# untitled.net
KiCad netlist of a schematic drawn in EAGLE
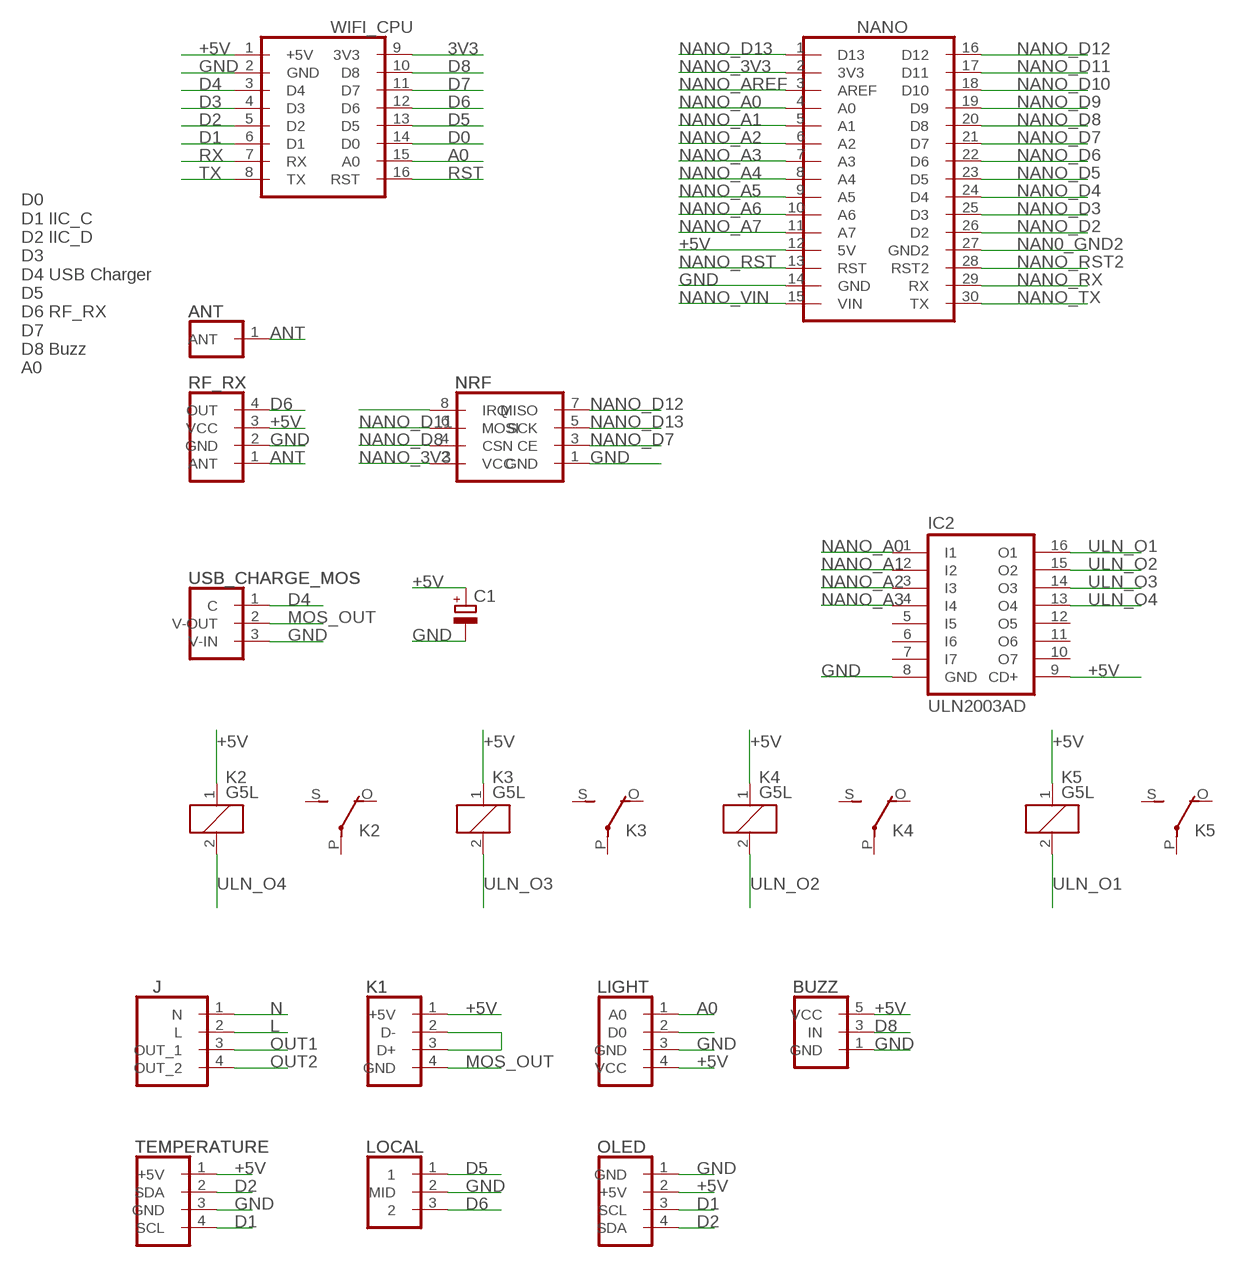
[diagram p0: schematic, sheet 1]

(export (version "E")
  (design (tool "Eeschema 10.0.6"))
  (components
    (comp (ref "ANT")
      (value "ANT_315")
      (footprint "eagle-import:ANT_315")
      (libsource (lib "eagle-import") (part "ANT_315"))
    )
    (comp (ref "BUZZ")
      (value "BUZZ_MODULE")
      (footprint "eagle-import:BUZZ_MODULE")
      (libsource (lib "eagle-import") (part "BUZZ_MODULE"))
    )
    (comp (ref "C1")
      (value "CPOL-EUE5-5")
      (footprint "eagle-import:E5-5")
      (libsource (lib "eagle-import") (part "CPOL-EUE5-5"))
    )
    (comp (ref "IC2")
      (value "ULN2003AD")
      (footprint "eagle-import:SO16")
      (libsource (lib "eagle-import") (part "ULN2003AD"))
    )
    (comp (ref "J")
      (value "OUT_HEAD_4_AC_2CH")
      (footprint "eagle-import:OUT_HEAD_4_AC_2CH")
      (libsource (lib "eagle-import") (part "OUT_HEAD_4_AC_2CH"))
    )
    (comp (ref "K1")
      (value "USB_OUTUSB_V")
      (footprint "eagle-import:USB_V_OUT")
      (libsource (lib "eagle-import") (part "USB_OUTUSB_V"))
    )
    (comp (ref "K2")
      (value "G5L")
      (footprint "eagle-import:G5LE")
      (libsource (lib "eagle-import") (part "G5L"))
    )
    (comp (ref "K3")
      (value "G5L")
      (footprint "eagle-import:G5LE")
      (libsource (lib "eagle-import") (part "G5L"))
    )
    (comp (ref "K4")
      (value "G5L")
      (footprint "eagle-import:G5LE")
      (libsource (lib "eagle-import") (part "G5L"))
    )
    (comp (ref "K5")
      (value "G5L")
      (footprint "eagle-import:G5LE")
      (libsource (lib "eagle-import") (part "G5L"))
    )
    (comp (ref "LIGHT")
      (value "LIGHT_DEC")
      (footprint "eagle-import:LIGHT_DEC")
      (libsource (lib "eagle-import") (part "LIGHT_DEC"))
    )
    (comp (ref "LOCAL")
      (value "SELECT_3")
      (footprint "eagle-import:SELECT_3")
      (libsource (lib "eagle-import") (part "SELECT_3"))
    )
    (comp (ref "NANO")
      (value "ARDUINO_NANO")
      (footprint "eagle-import:ARDUINO_NANO")
      (libsource (lib "eagle-import") (part "ARDUINO_NANO"))
    )
    (comp (ref "NRF")
      (value "NRF24L01_MODULE")
      (footprint "eagle-import:NRF24L01")
      (libsource (lib "eagle-import") (part "NRF24L01_MODULE"))
    )
    (comp (ref "OLED")
      (value "IIC_OLED")
      (footprint "eagle-import:IIC_OLED")
      (libsource (lib "eagle-import") (part "IIC_OLED"))
    )
    (comp (ref "RF_RX")
      (value "315MHZ_RX_SMT")
      (footprint "eagle-import:315MHZ_RX_SMT")
      (libsource (lib "eagle-import") (part "315MHZ_RX_SMT"))
    )
    (comp (ref "TEMPERATURE")
      (value "IIC_TEMPERATURE")
      (footprint "eagle-import:IIC_TEMPERATURE")
      (libsource (lib "eagle-import") (part "IIC_TEMPERATURE"))
    )
    (comp (ref "USB_CHARGE_MOS")
      (value "MOS_IRF520")
      (footprint "eagle-import:MOS_IRF520")
      (libsource (lib "eagle-import") (part "MOS_IRF520"))
    )
    (comp (ref "WIFI_CPU")
      (value "ESP8266_MINI")
      (footprint "eagle-import:ESP8266_MINI")
      (libsource (lib "eagle-import") (part "ESP8266_MINI"))
    )
  )
  (nets
    (net (code "1") (name "/+5V") (class "Default")
      (node (ref "BUZZ") (pin "5") (pinfunction "VCC_5") (pintype "bidirectional"))
      (node (ref "C1") (pin "+") (pinfunction "+_+") (pintype "passive"))
      (node (ref "IC2") (pin "9") (pinfunction "CD+_9") (pintype "passive"))
      (node (ref "K1") (pin "1") (pinfunction "+5V_1") (pintype "bidirectional"))
      (node (ref "K2") (pin "1") (pinfunction "1_1") (pintype "passive"))
      (node (ref "K3") (pin "1") (pinfunction "1_1") (pintype "passive"))
      (node (ref "K4") (pin "1") (pinfunction "1_1") (pintype "passive"))
      (node (ref "K5") (pin "1") (pinfunction "1_1") (pintype "passive"))
      (node (ref "LIGHT") (pin "4") (pinfunction "VCC_4") (pintype "bidirectional"))
      (node (ref "NANO") (pin "12") (pinfunction "5V_12") (pintype "bidirectional"))
      (node (ref "OLED") (pin "2") (pinfunction "+5V_2") (pintype "bidirectional"))
      (node (ref "RF_RX") (pin "3") (pinfunction "VCC_3") (pintype "bidirectional"))
      (node (ref "TEMPERATURE") (pin "1") (pinfunction "+5V_1") (pintype "bidirectional"))
      (node (ref "WIFI_CPU") (pin "1") (pinfunction "+5V_1") (pintype "bidirectional"))
    )
    (net (code "2") (name "/3V3") (class "Default")
      (node (ref "WIFI_CPU") (pin "9") (pinfunction "3V3_9") (pintype "bidirectional"))
    )
    (net (code "3") (name "/A0") (class "Default")
      (node (ref "LIGHT") (pin "1") (pinfunction "A0_1") (pintype "bidirectional"))
      (node (ref "WIFI_CPU") (pin "15") (pinfunction "A0_15") (pintype "bidirectional"))
    )
    (net (code "4") (name "/ANT") (class "Default")
      (node (ref "ANT") (pin "1") (pinfunction "ANT_1") (pintype "bidirectional"))
      (node (ref "RF_RX") (pin "1") (pinfunction "ANT_1") (pintype "bidirectional"))
    )
    (net (code "5") (name "/D0") (class "Default")
      (node (ref "WIFI_CPU") (pin "14") (pinfunction "D0_14") (pintype "bidirectional"))
    )
    (net (code "6") (name "/D1") (class "Default")
      (node (ref "OLED") (pin "3") (pinfunction "SCL_3") (pintype "bidirectional"))
      (node (ref "TEMPERATURE") (pin "4") (pinfunction "SCL_4") (pintype "bidirectional"))
      (node (ref "WIFI_CPU") (pin "6") (pinfunction "D1_6") (pintype "bidirectional"))
    )
    (net (code "7") (name "/D2") (class "Default")
      (node (ref "OLED") (pin "4") (pinfunction "SDA_4") (pintype "bidirectional"))
      (node (ref "TEMPERATURE") (pin "2") (pinfunction "SDA_2") (pintype "bidirectional"))
      (node (ref "WIFI_CPU") (pin "5") (pinfunction "D2_5") (pintype "bidirectional"))
    )
    (net (code "8") (name "/D3") (class "Default")
      (node (ref "WIFI_CPU") (pin "4") (pinfunction "D3_4") (pintype "bidirectional"))
    )
    (net (code "9") (name "/D4") (class "Default")
      (node (ref "USB_CHARGE_MOS") (pin "1") (pinfunction "C_1") (pintype "bidirectional"))
      (node (ref "WIFI_CPU") (pin "3") (pinfunction "D4_3") (pintype "bidirectional"))
    )
    (net (code "10") (name "/D5") (class "Default")
      (node (ref "LOCAL") (pin "1") (pinfunction "1_1") (pintype "bidirectional"))
      (node (ref "WIFI_CPU") (pin "13") (pinfunction "D5_13") (pintype "bidirectional"))
    )
    (net (code "11") (name "/D6") (class "Default")
      (node (ref "LOCAL") (pin "3") (pinfunction "2_3") (pintype "bidirectional"))
      (node (ref "RF_RX") (pin "4") (pinfunction "OUT_4") (pintype "bidirectional"))
      (node (ref "WIFI_CPU") (pin "12") (pinfunction "D6_12") (pintype "bidirectional"))
    )
    (net (code "12") (name "/D7") (class "Default")
      (node (ref "WIFI_CPU") (pin "11") (pinfunction "D7_11") (pintype "bidirectional"))
    )
    (net (code "13") (name "/D8") (class "Default")
      (node (ref "BUZZ") (pin "3") (pinfunction "IN_3") (pintype "bidirectional"))
      (node (ref "WIFI_CPU") (pin "10") (pinfunction "D8_10") (pintype "bidirectional"))
    )
    (net (code "14") (name "/GND") (class "Default")
      (node (ref "BUZZ") (pin "1") (pinfunction "GND_1") (pintype "bidirectional"))
      (node (ref "C1") (pin "-") (pinfunction "-_-") (pintype "passive"))
      (node (ref "IC2") (pin "8") (pinfunction "GND_8") (pintype "power_in"))
      (node (ref "LIGHT") (pin "3") (pinfunction "GND_3") (pintype "bidirectional"))
      (node (ref "LOCAL") (pin "2") (pinfunction "MID_2") (pintype "bidirectional"))
      (node (ref "NANO") (pin "14") (pinfunction "GND_14") (pintype "bidirectional"))
      (node (ref "NRF") (pin "1") (pinfunction "GND_1") (pintype "bidirectional"))
      (node (ref "OLED") (pin "1") (pinfunction "GND_1") (pintype "bidirectional"))
      (node (ref "RF_RX") (pin "2") (pinfunction "GND_2") (pintype "bidirectional"))
      (node (ref "TEMPERATURE") (pin "3") (pinfunction "GND_3") (pintype "bidirectional"))
      (node (ref "USB_CHARGE_MOS") (pin "3") (pinfunction "V-IN_3") (pintype "bidirectional"))
      (node (ref "WIFI_CPU") (pin "2") (pinfunction "GND_2") (pintype "bidirectional"))
    )
    (net (code "15") (name "/L") (class "Default")
      (node (ref "J") (pin "2") (pinfunction "L_2") (pintype "bidirectional"))
    )
    (net (code "16") (name "/MOS_OUT") (class "Default")
      (node (ref "K1") (pin "4") (pinfunction "GND_4") (pintype "bidirectional"))
      (node (ref "USB_CHARGE_MOS") (pin "2") (pinfunction "V-OUT_2") (pintype "bidirectional"))
    )
    (net (code "17") (name "/N") (class "Default")
      (node (ref "J") (pin "1") (pinfunction "N_1") (pintype "bidirectional"))
    )
    (net (code "18") (name "/NAN0_GND2") (class "Default")
      (node (ref "NANO") (pin "27") (pinfunction "GND2_27") (pintype "bidirectional"))
    )
    (net (code "19") (name "/NANO_3V3") (class "Default")
      (node (ref "NANO") (pin "2") (pinfunction "3V3_2") (pintype "bidirectional"))
      (node (ref "NRF") (pin "2") (pinfunction "VCC_2") (pintype "bidirectional"))
    )
    (net (code "20") (name "/NANO_A0") (class "Default")
      (node (ref "IC2") (pin "1") (pinfunction "I1_1") (pintype "input"))
      (node (ref "NANO") (pin "4") (pinfunction "A0_4") (pintype "bidirectional"))
    )
    (net (code "21") (name "/NANO_A1") (class "Default")
      (node (ref "IC2") (pin "2") (pinfunction "I2_2") (pintype "input"))
      (node (ref "NANO") (pin "5") (pinfunction "A1_5") (pintype "bidirectional"))
    )
    (net (code "22") (name "/NANO_A2") (class "Default")
      (node (ref "IC2") (pin "3") (pinfunction "I3_3") (pintype "input"))
      (node (ref "NANO") (pin "6") (pinfunction "A2_6") (pintype "bidirectional"))
    )
    (net (code "23") (name "/NANO_A3") (class "Default")
      (node (ref "IC2") (pin "4") (pinfunction "I4_4") (pintype "input"))
      (node (ref "NANO") (pin "7") (pinfunction "A3_7") (pintype "bidirectional"))
    )
    (net (code "24") (name "/NANO_A4") (class "Default")
      (node (ref "NANO") (pin "8") (pinfunction "A4_8") (pintype "bidirectional"))
    )
    (net (code "25") (name "/NANO_A5") (class "Default")
      (node (ref "NANO") (pin "9") (pinfunction "A5_9") (pintype "bidirectional"))
    )
    (net (code "26") (name "/NANO_A6") (class "Default")
      (node (ref "NANO") (pin "10") (pinfunction "A6_10") (pintype "bidirectional"))
    )
    (net (code "27") (name "/NANO_A7") (class "Default")
      (node (ref "NANO") (pin "11") (pinfunction "A7_11") (pintype "bidirectional"))
    )
    (net (code "28") (name "/NANO_AREF") (class "Default")
      (node (ref "NANO") (pin "3") (pinfunction "AREF_3") (pintype "bidirectional"))
    )
    (net (code "29") (name "/NANO_D2") (class "Default")
      (node (ref "NANO") (pin "26") (pinfunction "D2_26") (pintype "bidirectional"))
    )
    (net (code "30") (name "/NANO_D3") (class "Default")
      (node (ref "NANO") (pin "25") (pinfunction "D3_25") (pintype "bidirectional"))
    )
    (net (code "31") (name "/NANO_D4") (class "Default")
      (node (ref "NANO") (pin "24") (pinfunction "D4_24") (pintype "bidirectional"))
    )
    (net (code "32") (name "/NANO_D5") (class "Default")
      (node (ref "NANO") (pin "23") (pinfunction "D5_23") (pintype "bidirectional"))
    )
    (net (code "33") (name "/NANO_D6") (class "Default")
      (node (ref "NANO") (pin "22") (pinfunction "D6_22") (pintype "bidirectional"))
    )
    (net (code "34") (name "/NANO_D7") (class "Default")
      (node (ref "NANO") (pin "21") (pinfunction "D7_21") (pintype "bidirectional"))
      (node (ref "NRF") (pin "3") (pinfunction "CE_3") (pintype "bidirectional"))
    )
    (net (code "35") (name "/NANO_D8") (class "Default")
      (node (ref "NANO") (pin "20") (pinfunction "D8_20") (pintype "bidirectional"))
      (node (ref "NRF") (pin "4") (pinfunction "CSN_4") (pintype "bidirectional"))
    )
    (net (code "36") (name "/NANO_D9") (class "Default")
      (node (ref "NANO") (pin "19") (pinfunction "D9_19") (pintype "bidirectional"))
    )
    (net (code "37") (name "/NANO_D10") (class "Default")
      (node (ref "NANO") (pin "18") (pinfunction "D10_18") (pintype "bidirectional"))
    )
    (net (code "38") (name "/NANO_D11") (class "Default")
      (node (ref "NANO") (pin "17") (pinfunction "D11_17") (pintype "bidirectional"))
      (node (ref "NRF") (pin "6") (pinfunction "MOSI_6") (pintype "bidirectional"))
    )
    (net (code "39") (name "/NANO_D12") (class "Default")
      (node (ref "NANO") (pin "16") (pinfunction "D12_16") (pintype "bidirectional"))
      (node (ref "NRF") (pin "7") (pinfunction "MISO_7") (pintype "bidirectional"))
    )
    (net (code "40") (name "/NANO_D13") (class "Default")
      (node (ref "NANO") (pin "1") (pinfunction "D13_1") (pintype "bidirectional"))
      (node (ref "NRF") (pin "5") (pinfunction "SCK_5") (pintype "bidirectional"))
    )
    (net (code "41") (name "/NANO_RST") (class "Default")
      (node (ref "NANO") (pin "13") (pinfunction "RST_13") (pintype "bidirectional"))
    )
    (net (code "42") (name "/NANO_RST2") (class "Default")
      (node (ref "NANO") (pin "28") (pinfunction "RST2_28") (pintype "bidirectional"))
    )
    (net (code "43") (name "/NANO_RX") (class "Default")
      (node (ref "NANO") (pin "29") (pinfunction "RX_29") (pintype "bidirectional"))
    )
    (net (code "44") (name "/NANO_TX") (class "Default")
      (node (ref "NANO") (pin "30") (pinfunction "TX_30") (pintype "bidirectional"))
    )
    (net (code "45") (name "/NANO_VIN") (class "Default")
      (node (ref "NANO") (pin "15") (pinfunction "VIN_15") (pintype "bidirectional"))
    )
    (net (code "46") (name "/OUT1") (class "Default")
      (node (ref "J") (pin "3") (pinfunction "OUT_1_3") (pintype "bidirectional"))
    )
    (net (code "47") (name "/OUT2") (class "Default")
      (node (ref "J") (pin "4") (pinfunction "OUT_2_4") (pintype "bidirectional"))
    )
    (net (code "48") (name "/RST") (class "Default")
      (node (ref "WIFI_CPU") (pin "16") (pinfunction "RST_16") (pintype "bidirectional"))
    )
    (net (code "49") (name "/RX") (class "Default")
      (node (ref "WIFI_CPU") (pin "7") (pinfunction "RX_7") (pintype "bidirectional"))
    )
    (net (code "50") (name "/TX") (class "Default")
      (node (ref "WIFI_CPU") (pin "8") (pinfunction "TX_8") (pintype "bidirectional"))
    )
    (net (code "51") (name "/ULN_O1") (class "Default")
      (node (ref "IC2") (pin "16") (pinfunction "O1_16") (pintype "open_collector"))
      (node (ref "K5") (pin "2") (pinfunction "2_2") (pintype "passive"))
    )
    (net (code "52") (name "/ULN_O2") (class "Default")
      (node (ref "IC2") (pin "15") (pinfunction "O2_15") (pintype "open_collector"))
      (node (ref "K4") (pin "2") (pinfunction "2_2") (pintype "passive"))
    )
    (net (code "53") (name "/ULN_O3") (class "Default")
      (node (ref "IC2") (pin "14") (pinfunction "O3_14") (pintype "open_collector"))
      (node (ref "K3") (pin "2") (pinfunction "2_2") (pintype "passive"))
    )
    (net (code "54") (name "/ULN_O4") (class "Default")
      (node (ref "IC2") (pin "13") (pinfunction "O4_13") (pintype "open_collector"))
      (node (ref "K2") (pin "2") (pinfunction "2_2") (pintype "passive"))
    )
    (net (code "55") (name "Net-(K1-D+)") (class "Default")
      (node (ref "K1") (pin "2") (pinfunction "D-_2") (pintype "bidirectional"))
      (node (ref "K1") (pin "3") (pinfunction "D+_3") (pintype "bidirectional"))
    )
    (net (code "56") (name "unconnected-(IC2-I5-Pad5)") (class "Default")
      (node (ref "IC2") (pin "5") (pinfunction "I5_5") (pintype "input"))
    )
    (net (code "57") (name "unconnected-(IC2-I6-Pad6)") (class "Default")
      (node (ref "IC2") (pin "6") (pinfunction "I6_6") (pintype "input"))
    )
    (net (code "58") (name "unconnected-(IC2-I7-Pad7)") (class "Default")
      (node (ref "IC2") (pin "7") (pinfunction "I7_7") (pintype "input"))
    )
    (net (code "59") (name "unconnected-(IC2-O5-Pad12)") (class "Default")
      (node (ref "IC2") (pin "12") (pinfunction "O5_12") (pintype "open_collector"))
    )
    (net (code "60") (name "unconnected-(IC2-O6-Pad11)") (class "Default")
      (node (ref "IC2") (pin "11") (pinfunction "O6_11") (pintype "open_collector"))
    )
    (net (code "61") (name "unconnected-(IC2-O7-Pad10)") (class "Default")
      (node (ref "IC2") (pin "10") (pinfunction "O7_10") (pintype "open_collector"))
    )
    (net (code "62") (name "unconnected-(K2-PadO)") (class "Default")
      (node (ref "K2") (pin "O") (pinfunction "O_O") (pintype "passive"))
    )
    (net (code "63") (name "unconnected-(K2-PadP)") (class "Default")
      (node (ref "K2") (pin "P") (pinfunction "P_P") (pintype "passive"))
    )
    (net (code "64") (name "unconnected-(K2-PadS)") (class "Default")
      (node (ref "K2") (pin "S") (pinfunction "S_S") (pintype "passive"))
    )
    (net (code "65") (name "unconnected-(K3-PadO)") (class "Default")
      (node (ref "K3") (pin "O") (pinfunction "O_O") (pintype "passive"))
    )
    (net (code "66") (name "unconnected-(K3-PadP)") (class "Default")
      (node (ref "K3") (pin "P") (pinfunction "P_P") (pintype "passive"))
    )
    (net (code "67") (name "unconnected-(K3-PadS)") (class "Default")
      (node (ref "K3") (pin "S") (pinfunction "S_S") (pintype "passive"))
    )
    (net (code "68") (name "unconnected-(K4-PadO)") (class "Default")
      (node (ref "K4") (pin "O") (pinfunction "O_O") (pintype "passive"))
    )
    (net (code "69") (name "unconnected-(K4-PadP)") (class "Default")
      (node (ref "K4") (pin "P") (pinfunction "P_P") (pintype "passive"))
    )
    (net (code "70") (name "unconnected-(K4-PadS)") (class "Default")
      (node (ref "K4") (pin "S") (pinfunction "S_S") (pintype "passive"))
    )
    (net (code "71") (name "unconnected-(K5-PadO)") (class "Default")
      (node (ref "K5") (pin "O") (pinfunction "O_O") (pintype "passive"))
    )
    (net (code "72") (name "unconnected-(K5-PadP)") (class "Default")
      (node (ref "K5") (pin "P") (pinfunction "P_P") (pintype "passive"))
    )
    (net (code "73") (name "unconnected-(K5-PadS)") (class "Default")
      (node (ref "K5") (pin "S") (pinfunction "S_S") (pintype "passive"))
    )
    (net (code "74") (name "unconnected-(LIGHT-D0-Pad2)") (class "Default")
      (node (ref "LIGHT") (pin "2") (pinfunction "D0_2") (pintype "bidirectional"))
    )
    (net (code "75") (name "unconnected-(NRF-IRQ-Pad8)") (class "Default")
      (node (ref "NRF") (pin "8") (pinfunction "IRQ_8") (pintype "bidirectional"))
    )
  )
)
